# Sheet1.net
KiCad netlist of a schematic drawn in Altium Designer
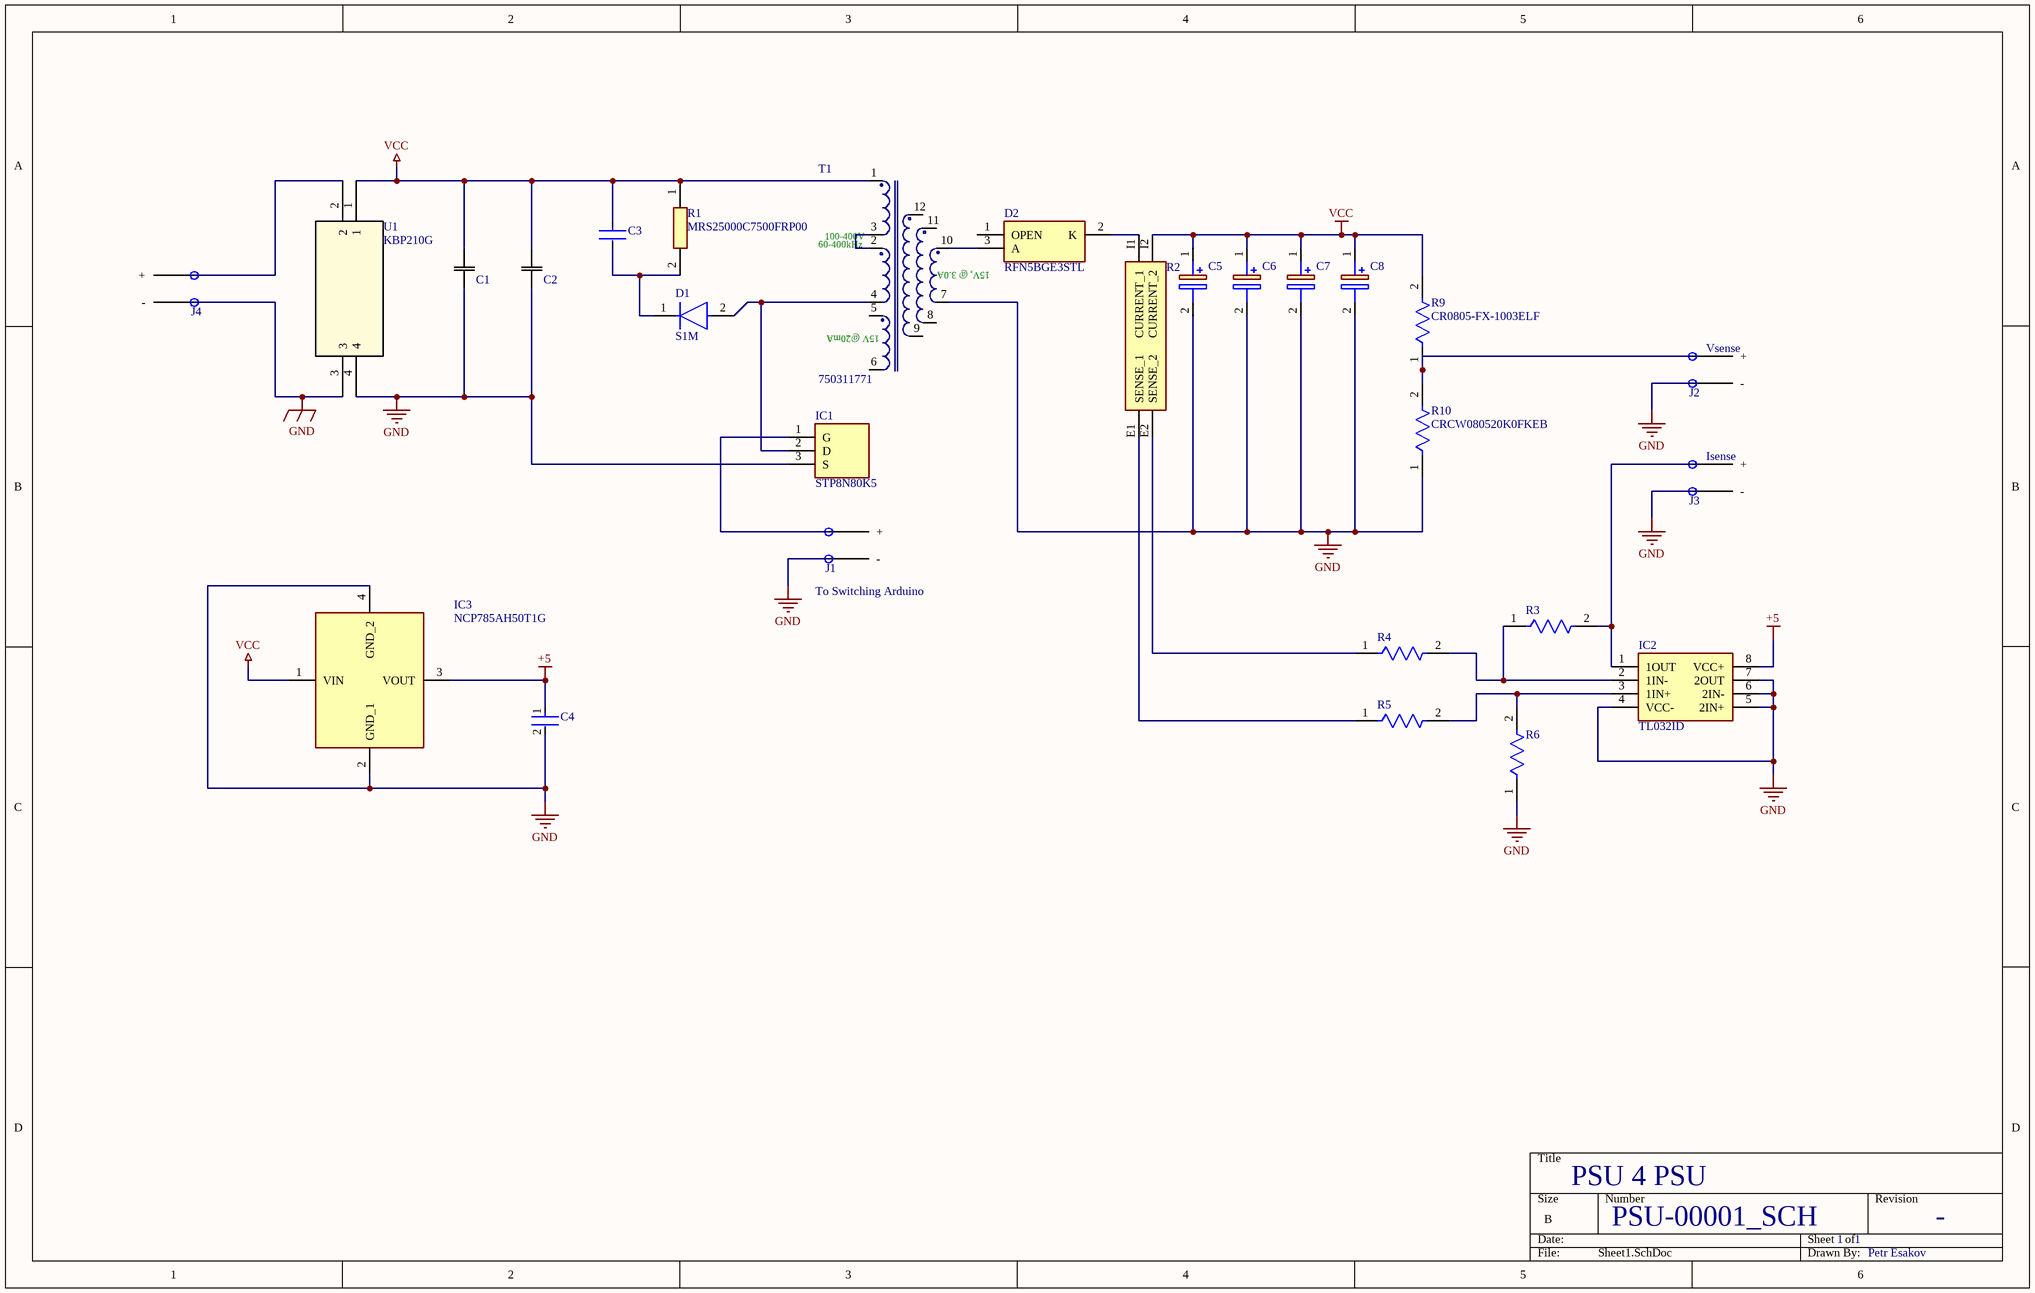
[diagram p0: Sheet1.SchDoc]

(export (version "E")
  (design (tool "Eeschema 10.0.6"))
  (components
    (comp (ref "C1")
      (value "500HXW100MEFR18X45")
      (footprint "CAP_HXW_18X45_RUB")
      (description "No Description Available")
      (libsource (lib "500HXW100MEFR18X45") (part "500HXW100MEFR18X45"))
    )
    (comp (ref "C2")
      (value "500HXW100MEFR18X45")
      (footprint "CAP_HXW_18X45_RUB")
      (description "No Description Available")
      (libsource (lib "500HXW100MEFR18X45") (part "500HXW100MEFR18X45"))
    )
    (comp (ref "C3")
      (value "GRM55DR72D105KW01L")
      (footprint "FP-GRM55D-0_4-MFG")
      (description "Chip Multilayer Ceramic Capacitors for General Purpose, 2220, 1.0uF, X7R, 15%, 10%, 200V")
      (fields (field (name "TOLERANCE") "10%"))
      (libsource (lib "") (part "b4654b650e69147ec39a6b967a45e02_1"))
    )
    (comp (ref "C4")
      (value "CGA6M3X7R2E104K200AE")
      (footprint "FP-CGA6P-IPC_A")
      (description "Cap Ceramic 100nF 250V X7R 10% Pad SMD 1210 +125°C Automotive T/R")
      (fields (field (name "TOLERANCE") "10%"))
      (libsource (lib "Altium Content Vault") (part "b4654b650e69147ec39a6b967a45e02"))
    )
    (comp (ref "C5")
      (value "EGXF630ELL511MK25S")
      (footprint "SamacSys:CAPPRD500W60D1275H2650")
      (description "Capacitor Polarised")
      (fields (field (name "MOUSER PART NUMBER") "661-EGXF630ELL511MK2"))
      (libsource (lib "*") (part "EGXF630ELL511MK25S"))
    )
    (comp (ref "C6")
      (value "EGXF630ELL511MK25S")
      (footprint "SamacSys:CAPPRD500W60D1275H2650")
      (description "Capacitor Polarised")
      (fields (field (name "MOUSER PART NUMBER") "661-EGXF630ELL511MK2"))
      (libsource (lib "*") (part "EGXF630ELL511MK25S"))
    )
    (comp (ref "C7")
      (value "EGXF630ELL511MK25S")
      (footprint "SamacSys:CAPPRD500W60D1275H2650")
      (description "Capacitor Polarised")
      (fields (field (name "MOUSER PART NUMBER") "661-EGXF630ELL511MK2"))
      (libsource (lib "*") (part "EGXF630ELL511MK25S"))
    )
    (comp (ref "C8")
      (value "EGXF630ELL511MK25S")
      (footprint "SamacSys:CAPPRD500W60D1275H2650")
      (description "Capacitor Polarised")
      (fields (field (name "MOUSER PART NUMBER") "661-EGXF630ELL511MK2"))
      (libsource (lib "*") (part "EGXF630ELL511MK25S"))
    )
    (comp (ref "D1")
      (value "S1M")
      (footprint "FP-403AE-MFG")
      (description "DIODE GEN PURP 1KV 1A SMA")
      (fields (field (name "VOLTAGE") "1kV"))
      (libsource (lib "Altium Content Vault") (part "d7152d700b627762746794eb795d46e"))
    )
    (comp (ref "D2")
      (value "RFN5BGE3STL")
      (footprint "SamacSys:RD3P175SNFRATL")
      (description "Diode")
      (fields (field (name "MOUSER PART NUMBER") "755-RFN5BGE3STL"))
      (libsource (lib "*") (part "RFN5BGE3STL"))
    )
    (comp (ref "IC1")
      (value "STP8N80K5")
      (footprint "SamacSys:TO255P460X1020X2008-3P")
      (description "Integrated Circuit")
      (fields (field (name "MOUSER PART NUMBER") "511-STP8N80K5"))
      (libsource (lib "*") (part "STP8N80K5"))
    )
    (comp (ref "IC2")
      (value "TL032ID")
      (footprint "SamacSys:SOIC127P600X175-8N")
      (description "Integrated Circuit")
      (fields (field (name "MOUSER PART NUMBER") "595-TL032ID"))
      (libsource (lib "*") (part "TL032ID"))
    )
    (comp (ref "IC3")
      (value "NCP785AH50T1G")
      (footprint "SamacSys:NCP785AH50T1G")
      (description "Integrated Circuit")
      (fields (field (name "MOUSER PART NUMBER") "863-NCP785AH50T1G"))
      (libsource (lib "*") (part "NCP785AH50T1G"))
    )
    (comp (ref "J1")
      (value "Component_1")
      (footprint "PCBComponent_1")
      (libsource (lib "Integrated_Library1") (part "Component_1"))
    )
    (comp (ref "J2")
      (value "Component_1")
      (footprint "PCBComponent_1")
      (libsource (lib "Integrated_Library1") (part "Component_1"))
    )
    (comp (ref "J3")
      (value "Component_1")
      (footprint "PCBComponent_1")
      (libsource (lib "Integrated_Library1") (part "Component_1"))
    )
    (comp (ref "J4")
      (value "Component_1")
      (footprint "PCBComponent_1")
      (libsource (lib "Integrated_Library1") (part "Component_1"))
    )
    (comp (ref "R1")
      (value "MRS25000C7500FRP00")
      (footprint "SamacSys:RESAD1650W60L650D250")
      (description "Resistor")
      (libsource (lib "*") (part "MRS25000C7500FRP00"))
    )
    (comp (ref "R2")
      (value "Y14870R10000B9R")
      (footprint "SamacSys:Y14870R10000B9R")
      (description "Resistor")
      (fields (field (name "MOUSER PART NUMBER") "71-CSM25120R1000BST"))
      (libsource (lib "*") (part "Y14870R10000B9R"))
    )
    (comp (ref "R3")
      (value "CRCW0805330KFKEA")
      (footprint "FP-CRCW0805-e3-MFG")
      (description "RES Thick Film, 330kΩ, 1%, 0.125W, 100ppm/°C, 0805")
      (fields (field (name "TOLERANCE") "1%"))
      (libsource (lib "Altium Content Vault") (part "1029c3af85768c4190bb7ad29bc67b5"))
    )
    (comp (ref "R4")
      (value "CRCW080520K0FKEB")
      (footprint "FP-CRCW0805-e3-IPC_B")
      (description "RES Thick Film, 20kΩ, 1%, 0.125W, 100ppm/°C, 0805")
      (fields (field (name "TOLERANCE") "1%"))
      (libsource (lib "Altium Content Vault") (part "1029c3af85768c4190bb7ad29bc67b5"))
    )
    (comp (ref "R5")
      (value "CRCW080520K0FKEB")
      (footprint "FP-CRCW0805-e3-IPC_B")
      (description "RES Thick Film, 20kΩ, 1%, 0.125W, 100ppm/°C, 0805")
      (fields (field (name "TOLERANCE") "1%"))
      (libsource (lib "Altium Content Vault") (part "1029c3af85768c4190bb7ad29bc67b5"))
    )
    (comp (ref "R6")
      (value "CRCW0805330KFKEA")
      (footprint "FP-CRCW0805-e3-MFG")
      (description "RES Thick Film, 330kΩ, 1%, 0.125W, 100ppm/°C, 0805")
      (fields (field (name "TOLERANCE") "1%"))
      (libsource (lib "Altium Content Vault") (part "1029c3af85768c4190bb7ad29bc67b5"))
    )
    (comp (ref "R9")
      (value "CR0805-FX-1003ELF")
      (footprint "FP-CR0805-IPC_B")
      (description "Thick Film Chip Resistors 0805 100kΩ 0.125W 1% 100ppm/°C")
      (fields (field (name "TOLERANCE") "1%"))
      (libsource (lib "Altium Content Vault") (part "1029c3af85768c4190bb7ad29bc67b5"))
    )
    (comp (ref "R10")
      (value "CRCW080520K0FKEB")
      (footprint "FP-CRCW0805-e3-IPC_B")
      (description "RES Thick Film, 20kΩ, 1%, 0.125W, 100ppm/°C, 0805")
      (fields (field (name "TOLERANCE") "1%"))
      (libsource (lib "Altium Content Vault") (part "1029c3af85768c4190bb7ad29bc67b5"))
    )
    (comp (ref "T1")
      (value "750311771")
      (footprint "EFD25")
      (description "Flyback Transformer suitable or LT3573/ LT3574/ LT3575/ LT3748 WE-FB, Ui=100-400V")
      (fields (field (name "MANUFACTURER") "Wuerth Elektronik"))
      (libsource (lib "Altium Content Vault") (part "WE-750311771"))
    )
    (comp (ref "U1")
      (value "KBP210G")
      (footprint "TO_P2005G_DIO")
      (description "No Description Available")
      (libsource (lib "KBP210G") (part "KBP210G"))
    )
  )
  (nets
    (net (code "1") (name "+5") (class "Default")
      (node (ref "C4") (pin "1") (pinfunction "1_1") (pintype "passive"))
      (node (ref "IC2") (pin "8") (pinfunction "VCC+_8") (pintype "passive"))
      (node (ref "IC3") (pin "3") (pinfunction "VOUT_3") (pintype "passive"))
    )
    (net (code "2") (name "GND") (class "Default")
      (node (ref "C1") (pin "1") (pinfunction "1_1") (pintype "passive"))
      (node (ref "C2") (pin "1") (pinfunction "1_1") (pintype "passive"))
      (node (ref "C4") (pin "2") (pinfunction "2_2") (pintype "passive"))
      (node (ref "C5") (pin "2") (pinfunction "-_2") (pintype "passive"))
      (node (ref "C6") (pin "2") (pinfunction "-_2") (pintype "passive"))
      (node (ref "C7") (pin "2") (pinfunction "-_2") (pintype "passive"))
      (node (ref "C8") (pin "2") (pinfunction "-_2") (pintype "passive"))
      (node (ref "IC1") (pin "3") (pinfunction "S_3") (pintype "passive"))
      (node (ref "IC2") (pin "4") (pinfunction "VCC-_4") (pintype "passive"))
      (node (ref "IC2") (pin "5") (pinfunction "2IN+_5") (pintype "passive"))
      (node (ref "IC2") (pin "6") (pinfunction "2IN-_6") (pintype "passive"))
      (node (ref "IC2") (pin "7") (pinfunction "2OUT_7") (pintype "passive"))
      (node (ref "IC3") (pin "2") (pinfunction "GND_1_2") (pintype "passive"))
      (node (ref "IC3") (pin "4") (pinfunction "GND_2_4") (pintype "passive"))
      (node (ref "J1") (pin "1") (pinfunction "-_1") (pintype "passive"))
      (node (ref "J2") (pin "1") (pinfunction "-_1") (pintype "passive"))
      (node (ref "J3") (pin "1") (pinfunction "-_1") (pintype "passive"))
      (node (ref "J4") (pin "1") (pinfunction "-_1") (pintype "passive"))
      (node (ref "R10") (pin "1") (pinfunction "1_1") (pintype "passive"))
      (node (ref "R6") (pin "1") (pinfunction "1_1") (pintype "passive"))
      (node (ref "T1") (pin "7") (pinfunction "7_7") (pintype "passive"))
      (node (ref "U1") (pin "3") (pinfunction "3_3") (pintype "passive"))
      (node (ref "U1") (pin "4") (pinfunction "4_4") (pintype "passive"))
    )
    (net (code "3") (name "Net-(D1-A)") (class "Default")
      (node (ref "D1") (pin "2") (pinfunction "A_2") (pintype "passive"))
      (node (ref "IC1") (pin "2") (pinfunction "D_2") (pintype "passive"))
      (node (ref "T1") (pin "4") (pinfunction "4_4") (pintype "passive"))
    )
    (net (code "4") (name "Net-(D1-C)") (class "Default")
      (node (ref "C3") (pin "2") (pinfunction "2_2") (pintype "passive"))
      (node (ref "D1") (pin "1") (pinfunction "C_1") (pintype "passive"))
      (node (ref "R1") (pin "2") (pinfunction "2_2") (pintype "passive"))
    )
    (net (code "5") (name "Net-(D2-A)") (class "Default")
      (node (ref "D2") (pin "3") (pinfunction "A_3") (pintype "passive"))
      (node (ref "T1") (pin "10") (pinfunction "10_10") (pintype "passive"))
    )
    (net (code "6") (name "Net-(D2-K)") (class "Default")
      (node (ref "D2") (pin "2") (pinfunction "K_2") (pintype "passive"))
      (node (ref "R2") (pin "I1") (pinfunction "CURRENT_1_I1") (pintype "passive"))
    )
    (net (code "7") (name "Net-(IC1-G)") (class "Default")
      (node (ref "IC1") (pin "1") (pinfunction "G_1") (pintype "passive"))
      (node (ref "J1") (pin "0") (pinfunction "+_0") (pintype "passive"))
    )
    (net (code "8") (name "Net-(IC2-1IN+)") (class "Default")
      (node (ref "IC2") (pin "3") (pinfunction "1IN+_3") (pintype "passive"))
      (node (ref "R5") (pin "2") (pinfunction "2_2") (pintype "passive"))
      (node (ref "R6") (pin "2") (pinfunction "2_2") (pintype "passive"))
    )
    (net (code "9") (name "Net-(IC2-1IN-)") (class "Default")
      (node (ref "IC2") (pin "2") (pinfunction "1IN-_2") (pintype "passive"))
      (node (ref "R3") (pin "1") (pinfunction "1_1") (pintype "passive"))
      (node (ref "R4") (pin "2") (pinfunction "2_2") (pintype "passive"))
    )
    (net (code "10") (name "Net-(IC2-1OUT)") (class "Default")
      (node (ref "IC2") (pin "1") (pinfunction "1OUT_1") (pintype "passive"))
      (node (ref "J3") (pin "0") (pinfunction "+_0") (pintype "passive"))
      (node (ref "R3") (pin "2") (pinfunction "2_2") (pintype "passive"))
    )
    (net (code "11") (name "Net-(J2-+)") (class "Default")
      (node (ref "J2") (pin "0") (pinfunction "+_0") (pintype "passive"))
      (node (ref "R10") (pin "2") (pinfunction "2_2") (pintype "passive"))
      (node (ref "R9") (pin "1") (pinfunction "1_1") (pintype "passive"))
    )
    (net (code "12") (name "Net-(J4-+)") (class "Default")
      (node (ref "J4") (pin "0") (pinfunction "+_0") (pintype "passive"))
      (node (ref "U1") (pin "2") (pinfunction "2_2") (pintype "passive"))
    )
    (net (code "13") (name "Net-(R2-SENSE_1)") (class "Default")
      (node (ref "R2") (pin "E1") (pinfunction "SENSE_1_E1") (pintype "passive"))
      (node (ref "R5") (pin "1") (pinfunction "1_1") (pintype "passive"))
    )
    (net (code "14") (name "Net-(R2-SENSE_2)") (class "Default")
      (node (ref "R2") (pin "E2") (pinfunction "SENSE_2_E2") (pintype "passive"))
      (node (ref "R4") (pin "1") (pinfunction "1_1") (pintype "passive"))
    )
    (net (code "15") (name "Net-(T1-Pad2)") (class "Default")
      (node (ref "T1") (pin "2") (pinfunction "2_2") (pintype "passive"))
      (node (ref "T1") (pin "3") (pinfunction "3_3") (pintype "passive"))
    )
    (net (code "16") (name "VCC") (class "Default")
      (node (ref "C1") (pin "2") (pinfunction "2_2") (pintype "passive"))
      (node (ref "C2") (pin "2") (pinfunction "2_2") (pintype "passive"))
      (node (ref "C3") (pin "1") (pinfunction "1_1") (pintype "passive"))
      (node (ref "C5") (pin "1") (pinfunction "+_1") (pintype "passive"))
      (node (ref "C6") (pin "1") (pinfunction "+_1") (pintype "passive"))
      (node (ref "C7") (pin "1") (pinfunction "+_1") (pintype "passive"))
      (node (ref "C8") (pin "1") (pinfunction "+_1") (pintype "passive"))
      (node (ref "IC3") (pin "1") (pinfunction "VIN_1") (pintype "passive"))
      (node (ref "R1") (pin "1") (pinfunction "1_1") (pintype "passive"))
      (node (ref "R2") (pin "I2") (pinfunction "CURRENT_2_I2") (pintype "passive"))
      (node (ref "R9") (pin "2") (pinfunction "2_2") (pintype "passive"))
      (node (ref "T1") (pin "1") (pinfunction "1_1") (pintype "passive"))
      (node (ref "U1") (pin "1") (pinfunction "1_1") (pintype "passive"))
    )
    (net (code "17") (name "unconnected-(D2-OPEN-Pad1)") (class "Default")
      (node (ref "D2") (pin "1") (pinfunction "OPEN_1") (pintype "passive"))
    )
    (net (code "18") (name "unconnected-(T1-Pad5)") (class "Default")
      (node (ref "T1") (pin "5") (pinfunction "5_5") (pintype "passive"))
    )
    (net (code "19") (name "unconnected-(T1-Pad6)") (class "Default")
      (node (ref "T1") (pin "6") (pinfunction "6_6") (pintype "passive"))
    )
    (net (code "20") (name "unconnected-(T1-Pad8)") (class "Default")
      (node (ref "T1") (pin "8") (pinfunction "8_8") (pintype "passive"))
    )
    (net (code "21") (name "unconnected-(T1-Pad9)") (class "Default")
      (node (ref "T1") (pin "9") (pinfunction "9_9") (pintype "passive"))
    )
    (net (code "22") (name "unconnected-(T1-Pad11)") (class "Default")
      (node (ref "T1") (pin "11") (pinfunction "11_11") (pintype "passive"))
    )
    (net (code "23") (name "unconnected-(T1-Pad12)") (class "Default")
      (node (ref "T1") (pin "12") (pinfunction "12_12") (pintype "passive"))
    )
  )
)
